# FabISP_Rev3.net
KiCad netlist of a schematic drawn in EAGLE
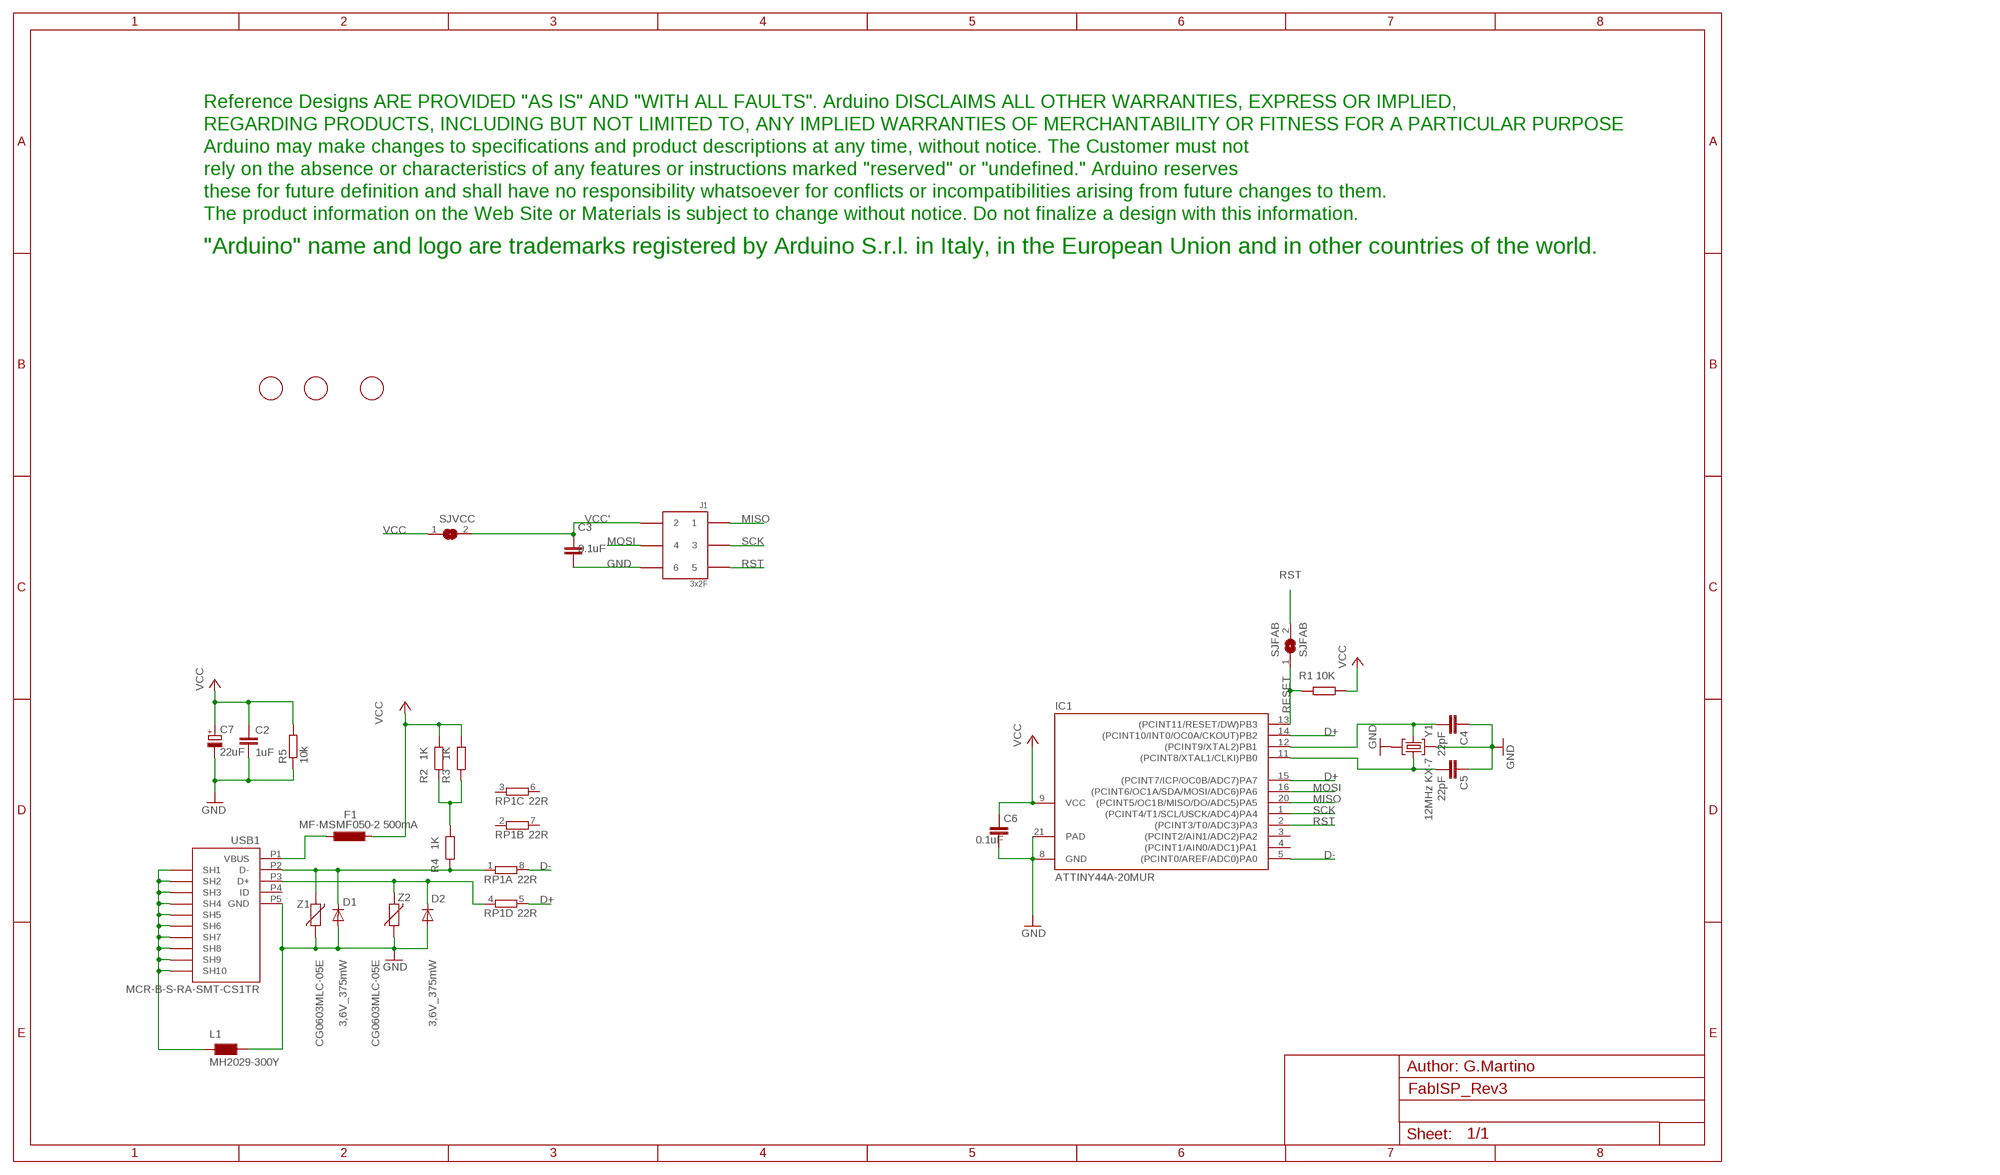
[diagram p0: schematic, sheet 1]

(export (version "E")
  (design (tool "Eeschema 10.0.6"))
  (components
    (comp (ref "C2")
      (value "1uF")
      (footprint "eagle-import:C0402")
      (libsource (lib "eagle-import") (part "C-EUC0402"))
    )
    (comp (ref "C3")
      (value "0.1uF")
      (footprint "eagle-import:C0402")
      (libsource (lib "eagle-import") (part "C-EUC0402"))
    )
    (comp (ref "C4")
      (value "22pF")
      (footprint "eagle-import:C0402")
      (libsource (lib "eagle-import") (part "C-EUC0402"))
    )
    (comp (ref "C5")
      (value "22pF")
      (footprint "eagle-import:C0402")
      (libsource (lib "eagle-import") (part "C-EUC0402"))
    )
    (comp (ref "C6")
      (value "0.1uF")
      (footprint "eagle-import:C0402")
      (libsource (lib "eagle-import") (part "C-EUC0402"))
    )
    (comp (ref "C7")
      (value "22uF")
      (footprint "eagle-import:SMC_B")
      (libsource (lib "eagle-import") (part "0167_"))
    )
    (comp (ref "D1")
      (value "3,6V_375mW")
      (footprint "eagle-import:SOD123")
      (fields (field (name "PART_NUMBER") "BZT52H-B3V6"))
      (libsource (lib "eagle-import") (part "0730_BZT52H-B3V6"))
    )
    (comp (ref "D2")
      (value "3,6V_375mW")
      (footprint "eagle-import:SOD123")
      (fields (field (name "PART_NUMBER") "BZT52H-B3V6"))
      (libsource (lib "eagle-import") (part "0730_BZT52H-B3V6"))
    )
    (comp (ref "F1")
      (value "MF-MSMF050-2 500mA")
      (footprint "eagle-import:L1812")
      (libsource (lib "eagle-import") (part "L-EUL1812"))
    )
    (comp (ref "IC1")
      (value "ATTINY44A-20MUR")
      (footprint "eagle-import:ATTINY24_44_84_QFN_MLF20")
      (libsource (lib "eagle-import") (part "ATTINY24_44_84_ATTINY24/44/84-MU"))
    )
    (comp (ref "J1")
      (value "3x2F")
      (footprint "eagle-import:HEAD3X2")
      (libsource (lib "eagle-import") (part "HEAD3X2"))
    )
    (comp (ref "L1")
      (value "MH2029-300Y")
      (footprint "eagle-import:0805")
      (fields (field (name "PART_NUMBER") "BLM21PG300SN1D_/_MH2029-300Y"))
      (libsource (lib "eagle-import") (part "0001_BLM21PG300SN1D_/_MH2029-300Y"))
    )
    (comp (ref "R1")
      (value "10K")
      (footprint "eagle-import:R0402")
      (libsource (lib "eagle-import") (part "R-EU_R0402"))
    )
    (comp (ref "R2")
      (value "1K")
      (footprint "eagle-import:R0402")
      (libsource (lib "eagle-import") (part "R-EU_R0402"))
    )
    (comp (ref "R3")
      (value "1K")
      (footprint "eagle-import:R0402")
      (libsource (lib "eagle-import") (part "R-EU_R0402"))
    )
    (comp (ref "R4")
      (value "1K")
      (footprint "eagle-import:R0402")
      (libsource (lib "eagle-import") (part "R-EU_R0402"))
    )
    (comp (ref "R5")
      (value "10k")
      (footprint "eagle-import:R0603-ROUND")
      (fields (field (name "PART_NUMBER") "CR0603JW103L"))
      (libsource (lib "eagle-import") (part "0028_CR0603JW103L"))
    )
    (comp (ref "RP1")
      (value "22R")
      (footprint "eagle-import:CAY16")
      (libsource (lib "eagle-import") (part "4R-NCAY16"))
    )
    (comp (ref "SJFAB")
      (value "SJFAB")
      (footprint "eagle-import:SJFAB")
      (libsource (lib "eagle-import") (part "SJFAB"))
    )
    (comp (ref "SJVCC")
      (value "SJFAB")
      (footprint "eagle-import:SJFAB")
      (libsource (lib "eagle-import") (part "SJFAB"))
    )
    (comp (ref "U$1")
      (value "FIDUCIALMOUNT")
      (footprint "eagle-import:FIDUCIA-MOUNT")
      (libsource (lib "eagle-import") (part "FIDUCIALMOUNT"))
    )
    (comp (ref "U$2")
      (value "FIDUCIALMOUNT")
      (footprint "eagle-import:FIDUCIA-MOUNT")
      (libsource (lib "eagle-import") (part "FIDUCIALMOUNT"))
    )
    (comp (ref "U$3")
      (value "FIDUCIALMOUNT")
      (footprint "eagle-import:FIDUCIA-MOUNT")
      (libsource (lib "eagle-import") (part "FIDUCIALMOUNT"))
    )
    (comp (ref "U$5")
      (value "DISCLAIMER")
      (footprint "eagle-import:DISCLAIMER")
      (libsource (lib "eagle-import") (part "DISCLAIMER"))
    )
    (comp (ref "USB1")
      (value "MCR-B-S-RA-SMT-CS1TR")
      (footprint "eagle-import:CON2_USB_MICRO_B_AT")
      (libsource (lib "eagle-import") (part "0158_MCR-B-S-RA-SMT-CS1TR"))
    )
    (comp (ref "Y1")
      (value "12MHz KX-7")
      (footprint "eagle-import:CRYSTAL-3.2-2.5")
      (libsource (lib "eagle-import") (part "CRYSTAL-3.2-2.5"))
    )
    (comp (ref "Z1")
      (value "CG0603MLC-05E")
      (footprint "eagle-import:CT_CN0603")
      (libsource (lib "eagle-import") (part "VARISTORCN0603"))
    )
    (comp (ref "Z2")
      (value "CG0603MLC-05E")
      (footprint "eagle-import:CT_CN0603")
      (libsource (lib "eagle-import") (part "VARISTORCN0603"))
    )
  )
  (nets
    (net (code "1") (name "/D+") (class "Default")
      (node (ref "IC1") (pin "14") (pinfunction "(PCINT10/INT0/OC0A/CKOUT)PB2_14") (pintype "bidirectional"))
      (node (ref "IC1") (pin "15") (pinfunction "(PCINT7/ICP/OC0B/ADC7)PA7_15") (pintype "bidirectional"))
      (node (ref "RP1") (pin "5") (pinfunction "2_5") (pintype "passive"))
    )
    (net (code "2") (name "/D-") (class "Default")
      (node (ref "IC1") (pin "5") (pinfunction "(PCINT0/AREF/ADC0)PA0_5") (pintype "bidirectional"))
      (node (ref "RP1") (pin "8") (pinfunction "2_8") (pintype "passive"))
    )
    (net (code "3") (name "/MISO") (class "Default")
      (node (ref "IC1") (pin "20") (pinfunction "(PCINT5/OC1B/MISO/DO/ADC5)PA5_20") (pintype "bidirectional"))
      (node (ref "J1") (pin "1") (pinfunction "1_1") (pintype "passive"))
    )
    (net (code "4") (name "/MOSI") (class "Default")
      (node (ref "IC1") (pin "16") (pinfunction "(PCINT6/OC1A/SDA/MOSI/ADC6)PA6_16") (pintype "bidirectional"))
      (node (ref "J1") (pin "4") (pinfunction "4_4") (pintype "passive"))
    )
    (net (code "5") (name "/RESET") (class "Default")
      (node (ref "IC1") (pin "13") (pinfunction "(PCINT11/RESET/DW)PB3_13") (pintype "bidirectional"))
      (node (ref "R1") (pin "1") (pinfunction "1_1") (pintype "passive"))
      (node (ref "SJFAB") (pin "1") (pinfunction "1_1") (pintype "passive"))
    )
    (net (code "6") (name "/RST") (class "Default")
      (node (ref "IC1") (pin "2") (pinfunction "(PCINT3/T0/ADC3)PA3_2") (pintype "bidirectional"))
      (node (ref "J1") (pin "5") (pinfunction "5_5") (pintype "passive"))
      (node (ref "SJFAB") (pin "2") (pinfunction "2_2") (pintype "passive"))
    )
    (net (code "7") (name "/SCK") (class "Default")
      (node (ref "IC1") (pin "1") (pinfunction "(PCINT4/T1/SCL/USCK/ADC4)PA4_1") (pintype "bidirectional"))
      (node (ref "J1") (pin "3") (pinfunction "3_3") (pintype "passive"))
    )
    (net (code "8") (name "/VCC'") (class "Default")
      (node (ref "C3") (pin "1") (pinfunction "1_1") (pintype "passive"))
      (node (ref "J1") (pin "2") (pinfunction "2_2") (pintype "passive"))
      (node (ref "SJVCC") (pin "2") (pinfunction "2_2") (pintype "passive"))
    )
    (net (code "9") (name "GND") (class "Default")
      (node (ref "C2") (pin "2") (pinfunction "2_2") (pintype "passive"))
      (node (ref "C3") (pin "2") (pinfunction "2_2") (pintype "passive"))
      (node (ref "C4") (pin "1") (pinfunction "1_1") (pintype "passive"))
      (node (ref "C5") (pin "1") (pinfunction "1_1") (pintype "passive"))
      (node (ref "C6") (pin "2") (pinfunction "2_2") (pintype "passive"))
      (node (ref "C7") (pin "-") (pinfunction "-_-") (pintype "passive"))
      (node (ref "D1") (pin "A") (pinfunction "A_A") (pintype "passive"))
      (node (ref "D2") (pin "A") (pinfunction "A_A") (pintype "passive"))
      (node (ref "IC1") (pin "21") (pinfunction "PAD_21") (pintype "power_in"))
      (node (ref "IC1") (pin "8") (pinfunction "GND_8") (pintype "power_in"))
      (node (ref "J1") (pin "6") (pinfunction "6_6") (pintype "passive"))
      (node (ref "L1") (pin "2") (pinfunction "2_2") (pintype "passive"))
      (node (ref "R5") (pin "1") (pinfunction "1_1") (pintype "passive"))
      (node (ref "USB1") (pin "P5") (pinfunction "GND_P5") (pintype "passive"))
      (node (ref "Y1") (pin "2") (pinfunction "GND_2") (pintype "passive"))
      (node (ref "Y1") (pin "4") (pinfunction "GND_4") (pintype "passive"))
      (node (ref "Z1") (pin "1") (pinfunction "1_1") (pintype "passive"))
      (node (ref "Z2") (pin "1") (pinfunction "1_1") (pintype "passive"))
    )
    (net (code "10") (name "Net-(IC1-(PCINT8{slash}XTAL1{slash}CLKI)PB0)") (class "Default")
      (node (ref "C5") (pin "2") (pinfunction "2_2") (pintype "passive"))
      (node (ref "IC1") (pin "11") (pinfunction "(PCINT8/XTAL1/CLKI)PB0_11") (pintype "bidirectional"))
      (node (ref "Y1") (pin "1") (pinfunction "C1_1") (pintype "passive"))
    )
    (net (code "11") (name "Net-(IC1-(PCINT9{slash}XTAL2)PB1)") (class "Default")
      (node (ref "C4") (pin "2") (pinfunction "2_2") (pintype "passive"))
      (node (ref "IC1") (pin "12") (pinfunction "(PCINT9/XTAL2)PB1_12") (pintype "bidirectional"))
      (node (ref "Y1") (pin "3") (pinfunction "C2_3") (pintype "passive"))
    )
    (net (code "12") (name "Net-(R2-Pad1)") (class "Default")
      (node (ref "R2") (pin "1") (pinfunction "1_1") (pintype "passive"))
      (node (ref "R3") (pin "1") (pinfunction "1_1") (pintype "passive"))
      (node (ref "R4") (pin "2") (pinfunction "2_2") (pintype "passive"))
    )
    (net (code "13") (name "Net-(RP1D-1)") (class "Default")
      (node (ref "D2") (pin "C") (pinfunction "C_C") (pintype "passive"))
      (node (ref "RP1") (pin "4") (pinfunction "1_4") (pintype "passive"))
      (node (ref "USB1") (pin "P3") (pinfunction "D+_P3") (pintype "bidirectional"))
      (node (ref "Z2") (pin "2") (pinfunction "2_2") (pintype "passive"))
    )
    (net (code "14") (name "Net-(USB1-D-)") (class "Default")
      (node (ref "D1") (pin "C") (pinfunction "C_C") (pintype "passive"))
      (node (ref "R4") (pin "1") (pinfunction "1_1") (pintype "passive"))
      (node (ref "RP1") (pin "1") (pinfunction "1_1") (pintype "passive"))
      (node (ref "USB1") (pin "P2") (pinfunction "D-_P2") (pintype "bidirectional"))
      (node (ref "Z1") (pin "2") (pinfunction "2_2") (pintype "passive"))
    )
    (net (code "15") (name "Net-(USB1-SH1)") (class "Default")
      (node (ref "L1") (pin "1") (pinfunction "1_1") (pintype "passive"))
      (node (ref "USB1") (pin "P$1") (pinfunction "SH7_P$1") (pintype "passive"))
      (node (ref "USB1") (pin "P$2") (pinfunction "SH8_P$2") (pintype "passive"))
      (node (ref "USB1") (pin "P$3") (pinfunction "SH9_P$3") (pintype "passive"))
      (node (ref "USB1") (pin "P$4") (pinfunction "SH10_P$4") (pintype "passive"))
      (node (ref "USB1") (pin "P$5") (pinfunction "SH7_P$5") (pintype "passive"))
      (node (ref "USB1") (pin "P$6") (pinfunction "SH8_P$6") (pintype "passive"))
      (node (ref "USB1") (pin "P$7") (pinfunction "SH9_P$7") (pintype "passive"))
      (node (ref "USB1") (pin "P$8") (pinfunction "SH10_P$8") (pintype "passive"))
      (node (ref "USB1") (pin "S1") (pinfunction "SH1_S1") (pintype "passive"))
      (node (ref "USB1") (pin "S2") (pinfunction "SH2_S2") (pintype "passive"))
      (node (ref "USB1") (pin "S3") (pinfunction "SH3_S3") (pintype "passive"))
      (node (ref "USB1") (pin "S4") (pinfunction "SH4_S4") (pintype "passive"))
      (node (ref "USB1") (pin "S5") (pinfunction "SH5_S5") (pintype "passive"))
      (node (ref "USB1") (pin "S6") (pinfunction "SH6_S6") (pintype "passive"))
    )
    (net (code "16") (name "Net-(USB1-VBUS)") (class "Default")
      (node (ref "F1") (pin "2") (pinfunction "2_2") (pintype "passive"))
      (node (ref "USB1") (pin "P1") (pinfunction "VBUS_P1") (pintype "power_in"))
    )
    (net (code "17") (name "VCC") (class "Default")
      (node (ref "C2") (pin "1") (pinfunction "1_1") (pintype "passive"))
      (node (ref "C6") (pin "1") (pinfunction "1_1") (pintype "passive"))
      (node (ref "C7") (pin "+") (pinfunction "+_+") (pintype "passive"))
      (node (ref "F1") (pin "1") (pinfunction "1_1") (pintype "passive"))
      (node (ref "IC1") (pin "9") (pinfunction "VCC_9") (pintype "power_in"))
      (node (ref "R1") (pin "2") (pinfunction "2_2") (pintype "passive"))
      (node (ref "R2") (pin "2") (pinfunction "2_2") (pintype "passive"))
      (node (ref "R3") (pin "2") (pinfunction "2_2") (pintype "passive"))
      (node (ref "R5") (pin "2") (pinfunction "2_2") (pintype "passive"))
      (node (ref "SJVCC") (pin "1") (pinfunction "1_1") (pintype "passive"))
    )
    (net (code "18") (name "unconnected-(IC1-(PCINT1{slash}AIN0{slash}ADC1)PA1-Pad4)") (class "Default")
      (node (ref "IC1") (pin "4") (pinfunction "(PCINT1/AIN0/ADC1)PA1_4") (pintype "bidirectional"))
    )
    (net (code "19") (name "unconnected-(IC1-(PCINT2{slash}AIN1{slash}ADC2)PA2-Pad3)") (class "Default")
      (node (ref "IC1") (pin "3") (pinfunction "(PCINT2/AIN1/ADC2)PA2_3") (pintype "bidirectional"))
    )
    (net (code "20") (name "unconnected-(RP1B-1-Pad2)") (class "Default")
      (node (ref "RP1") (pin "2") (pinfunction "1_2") (pintype "passive"))
    )
    (net (code "21") (name "unconnected-(RP1B-2-Pad7)") (class "Default")
      (node (ref "RP1") (pin "7") (pinfunction "2_7") (pintype "passive"))
    )
    (net (code "22") (name "unconnected-(RP1C-1-Pad3)") (class "Default")
      (node (ref "RP1") (pin "3") (pinfunction "1_3") (pintype "passive"))
    )
    (net (code "23") (name "unconnected-(RP1C-2-Pad6)") (class "Default")
      (node (ref "RP1") (pin "6") (pinfunction "2_6") (pintype "passive"))
    )
    (net (code "24") (name "unconnected-(USB1-ID-PadP4)") (class "Default")
      (node (ref "USB1") (pin "P4") (pinfunction "ID_P4") (pintype "bidirectional"))
    )
  )
)
